# ICEDevice.net
KiCad netlist of a schematic drawn in EAGLE
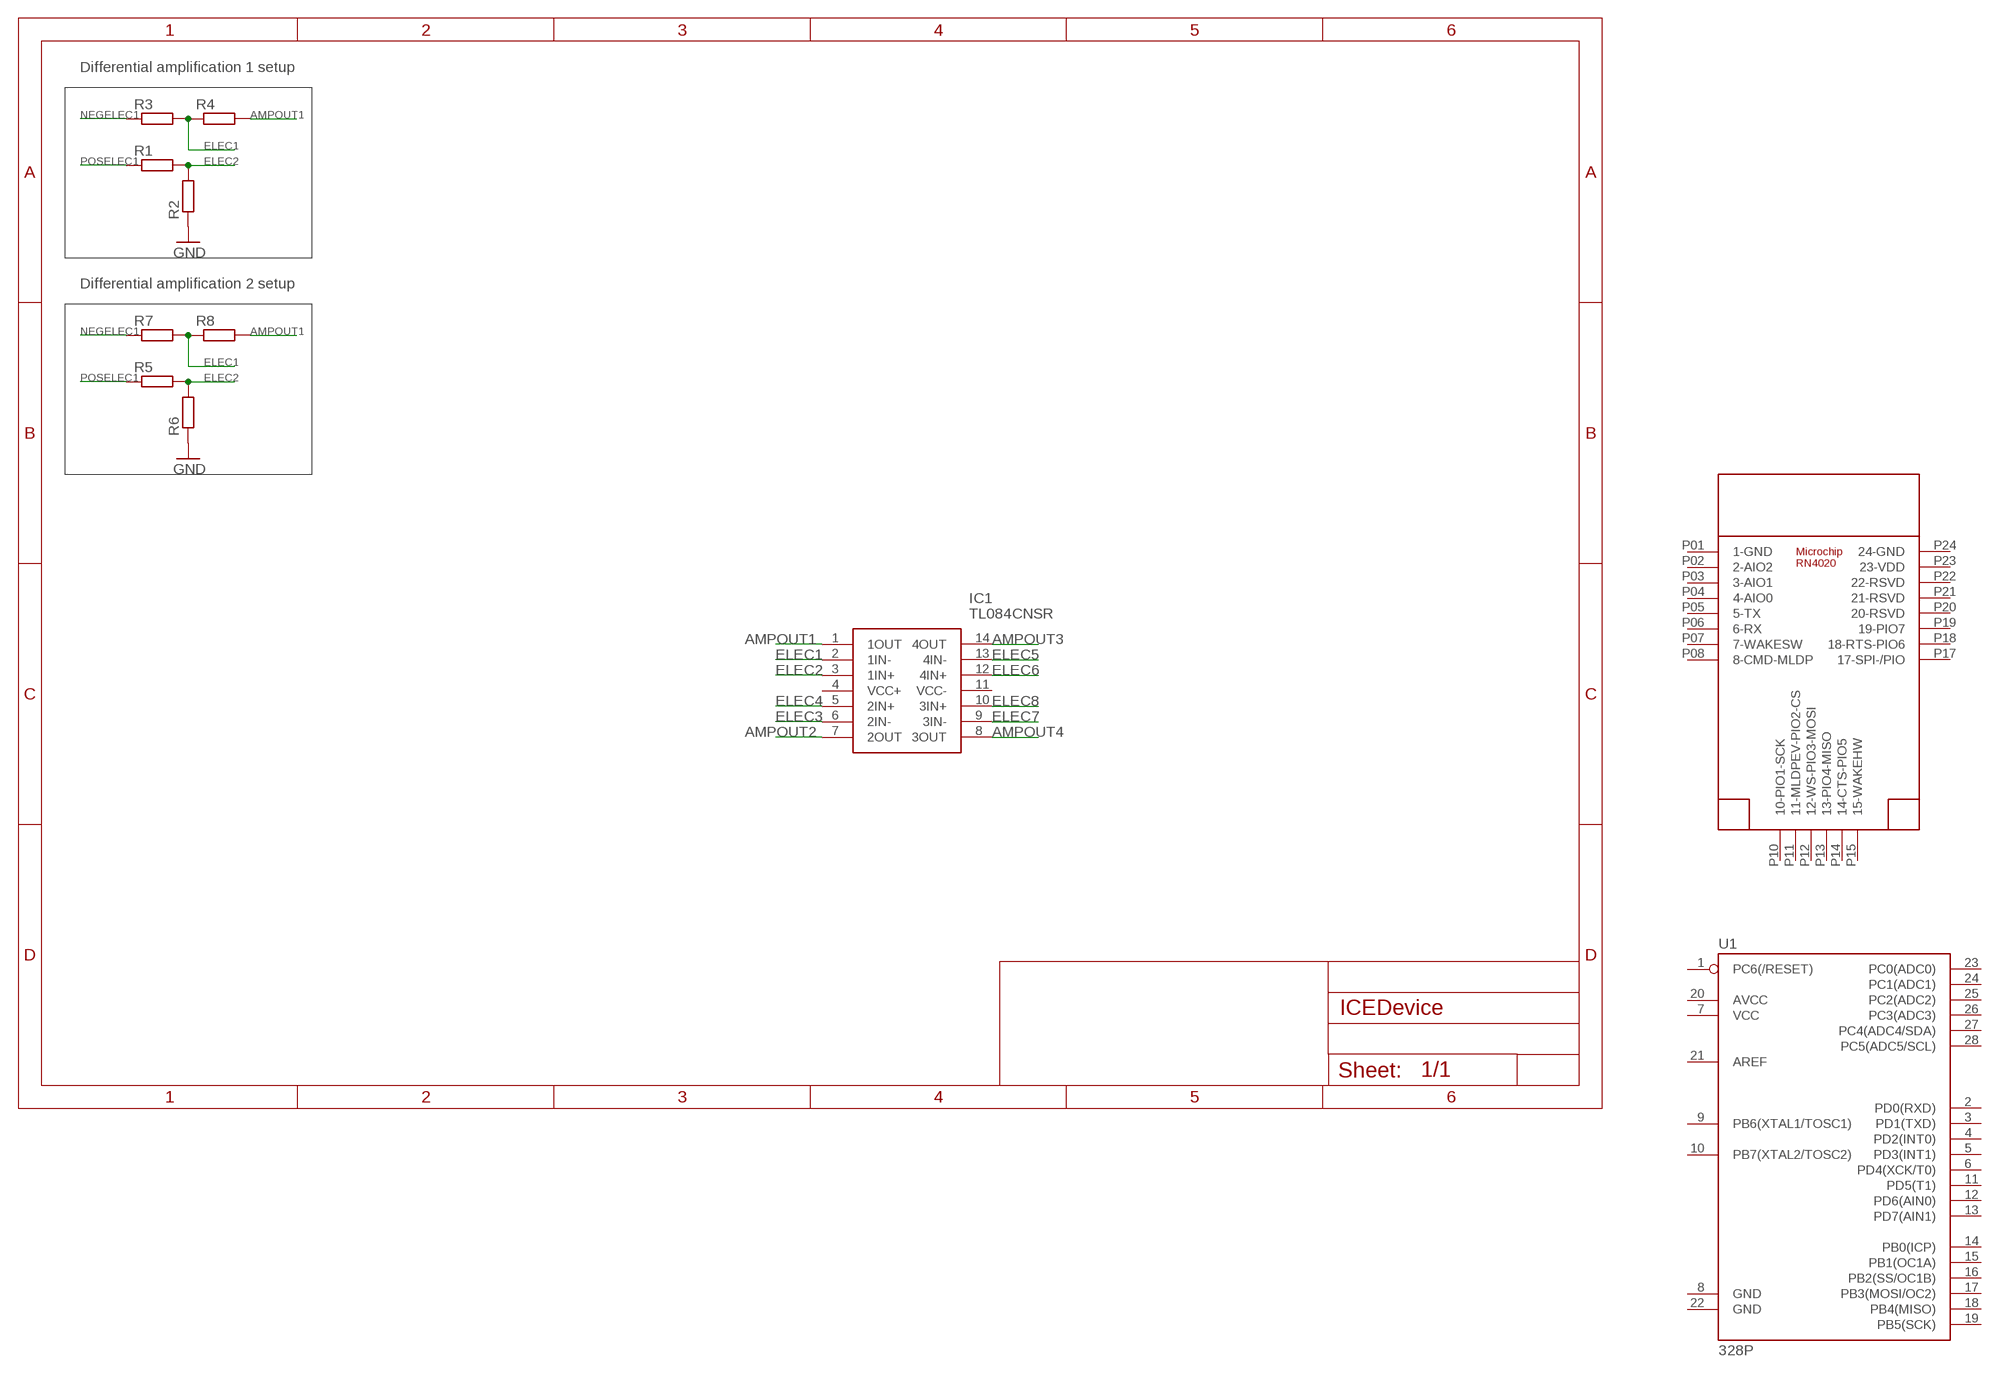
[diagram p0: schematic, sheet 1]

(export (version "E")
  (design (tool "Eeschema 10.0.6"))
  (components
    (comp (ref "IC1")
      (value "TL084CNSR")
      (footprint "eagle-import:SOIC127P780X200-14N")
      (fields (field (name "RS_PART_NUMBER") "1626742"))
      (libsource (lib "eagle-import") (part "TL084CNSR"))
    )
    (comp (ref "R1")
      (value "R-EU_0309/10")
      (footprint "eagle-import:0309_10")
      (libsource (lib "eagle-import") (part "R-EU_0309/10"))
    )
    (comp (ref "R2")
      (value "R-EU_0309/10")
      (footprint "eagle-import:0309_10")
      (libsource (lib "eagle-import") (part "R-EU_0309/10"))
    )
    (comp (ref "R3")
      (value "R-EU_0309/10")
      (footprint "eagle-import:0309_10")
      (libsource (lib "eagle-import") (part "R-EU_0309/10"))
    )
    (comp (ref "R4")
      (value "R-EU_0309/10")
      (footprint "eagle-import:0309_10")
      (libsource (lib "eagle-import") (part "R-EU_0309/10"))
    )
    (comp (ref "R5")
      (value "R-EU_0309/10")
      (footprint "eagle-import:0309_10")
      (libsource (lib "eagle-import") (part "R-EU_0309/10"))
    )
    (comp (ref "R6")
      (value "R-EU_0309/10")
      (footprint "eagle-import:0309_10")
      (libsource (lib "eagle-import") (part "R-EU_0309/10"))
    )
    (comp (ref "R7")
      (value "R-EU_0309/10")
      (footprint "eagle-import:0309_10")
      (libsource (lib "eagle-import") (part "R-EU_0309/10"))
    )
    (comp (ref "R8")
      (value "R-EU_0309/10")
      (footprint "eagle-import:0309_10")
      (libsource (lib "eagle-import") (part "R-EU_0309/10"))
    )
    (comp (ref "U$1")
      (value "RN4020")
      (footprint "eagle-import:RN4020SMD")
      (libsource (lib "eagle-import") (part "RN4020"))
    )
    (comp (ref "U1")
      (value "328P")
      (footprint "eagle-import:DIP28")
      (libsource (lib "eagle-import") (part "ATMEGA328P_PDIP"))
    )
  )
  (nets
    (net (code "1") (name "/AMPOUT1") (class "Default")
      (node (ref "IC1") (pin "1") (pinfunction "1OUT_1") (pintype "bidirectional"))
      (node (ref "R4") (pin "2") (pinfunction "2_2") (pintype "passive"))
      (node (ref "R8") (pin "2") (pinfunction "2_2") (pintype "passive"))
    )
    (net (code "2") (name "/AMPOUT2") (class "Default")
      (node (ref "IC1") (pin "7") (pinfunction "2OUT_7") (pintype "bidirectional"))
    )
    (net (code "3") (name "/AMPOUT3") (class "Default")
      (node (ref "IC1") (pin "14") (pinfunction "4OUT_14") (pintype "bidirectional"))
    )
    (net (code "4") (name "/AMPOUT4") (class "Default")
      (node (ref "IC1") (pin "8") (pinfunction "3OUT_8") (pintype "bidirectional"))
    )
    (net (code "5") (name "/ELEC1") (class "Default")
      (node (ref "IC1") (pin "2") (pinfunction "1IN-_2") (pintype "bidirectional"))
      (node (ref "R3") (pin "2") (pinfunction "2_2") (pintype "passive"))
      (node (ref "R4") (pin "1") (pinfunction "1_1") (pintype "passive"))
      (node (ref "R7") (pin "2") (pinfunction "2_2") (pintype "passive"))
      (node (ref "R8") (pin "1") (pinfunction "1_1") (pintype "passive"))
    )
    (net (code "6") (name "/ELEC2") (class "Default")
      (node (ref "IC1") (pin "3") (pinfunction "1IN+_3") (pintype "bidirectional"))
      (node (ref "R1") (pin "2") (pinfunction "2_2") (pintype "passive"))
      (node (ref "R2") (pin "2") (pinfunction "2_2") (pintype "passive"))
      (node (ref "R5") (pin "2") (pinfunction "2_2") (pintype "passive"))
      (node (ref "R6") (pin "2") (pinfunction "2_2") (pintype "passive"))
    )
    (net (code "7") (name "/ELEC3") (class "Default")
      (node (ref "IC1") (pin "6") (pinfunction "2IN-_6") (pintype "bidirectional"))
    )
    (net (code "8") (name "/ELEC4") (class "Default")
      (node (ref "IC1") (pin "5") (pinfunction "2IN+_5") (pintype "bidirectional"))
    )
    (net (code "9") (name "/ELEC5") (class "Default")
      (node (ref "IC1") (pin "13") (pinfunction "4IN-_13") (pintype "bidirectional"))
    )
    (net (code "10") (name "/ELEC6") (class "Default")
      (node (ref "IC1") (pin "12") (pinfunction "4IN+_12") (pintype "bidirectional"))
    )
    (net (code "11") (name "/ELEC7") (class "Default")
      (node (ref "IC1") (pin "9") (pinfunction "3IN-_9") (pintype "bidirectional"))
    )
    (net (code "12") (name "/ELEC8") (class "Default")
      (node (ref "IC1") (pin "10") (pinfunction "3IN+_10") (pintype "bidirectional"))
    )
    (net (code "13") (name "/NEGELEC1") (class "Default")
      (node (ref "R3") (pin "1") (pinfunction "1_1") (pintype "passive"))
      (node (ref "R7") (pin "1") (pinfunction "1_1") (pintype "passive"))
    )
    (net (code "14") (name "/POSELEC1") (class "Default")
      (node (ref "R1") (pin "1") (pinfunction "1_1") (pintype "passive"))
      (node (ref "R5") (pin "1") (pinfunction "1_1") (pintype "passive"))
    )
    (net (code "15") (name "GND") (class "Default")
      (node (ref "R2") (pin "1") (pinfunction "1_1") (pintype "passive"))
      (node (ref "R6") (pin "1") (pinfunction "1_1") (pintype "passive"))
    )
    (net (code "16") (name "unconnected-(IC1-VCC+-Pad4)") (class "Default")
      (node (ref "IC1") (pin "4") (pinfunction "VCC+_4") (pintype "bidirectional"))
    )
    (net (code "17") (name "unconnected-(IC1-VCC--Pad11)") (class "Default")
      (node (ref "IC1") (pin "11") (pinfunction "VCC-_11") (pintype "bidirectional"))
    )
    (net (code "18") (name "unconnected-(U$1-1-GND-PadP01)") (class "Default")
      (node (ref "U$1") (pin "P01") (pinfunction "1-GND_P01") (pintype "bidirectional"))
    )
    (net (code "19") (name "unconnected-(U$1-2-AIO2-PadP02)") (class "Default")
      (node (ref "U$1") (pin "P02") (pinfunction "2-AIO2_P02") (pintype "bidirectional"))
    )
    (net (code "20") (name "unconnected-(U$1-3-AIO1-PadP03)") (class "Default")
      (node (ref "U$1") (pin "P03") (pinfunction "3-AIO1_P03") (pintype "bidirectional"))
    )
    (net (code "21") (name "unconnected-(U$1-4-AIO0-PadP04)") (class "Default")
      (node (ref "U$1") (pin "P04") (pinfunction "4-AIO0_P04") (pintype "bidirectional"))
    )
    (net (code "22") (name "unconnected-(U$1-5-TX-PadP05)") (class "Default")
      (node (ref "U$1") (pin "P05") (pinfunction "5-TX_P05") (pintype "bidirectional"))
    )
    (net (code "23") (name "unconnected-(U$1-6-RX-PadP06)") (class "Default")
      (node (ref "U$1") (pin "P06") (pinfunction "6-RX_P06") (pintype "bidirectional"))
    )
    (net (code "24") (name "unconnected-(U$1-7-WAKESW-PadP07)") (class "Default")
      (node (ref "U$1") (pin "P07") (pinfunction "7-WAKESW_P07") (pintype "bidirectional"))
    )
    (net (code "25") (name "unconnected-(U$1-8-CMD-MLDP-PadP08)") (class "Default")
      (node (ref "U$1") (pin "P08") (pinfunction "8-CMD-MLDP_P08") (pintype "bidirectional"))
    )
    (net (code "26") (name "unconnected-(U$1-10-PIO1-SCK-PadP10)") (class "Default")
      (node (ref "U$1") (pin "P10") (pinfunction "10-PIO1-SCK_P10") (pintype "bidirectional"))
    )
    (net (code "27") (name "unconnected-(U$1-11-MLDPEV-PIO2-CS-PadP11)") (class "Default")
      (node (ref "U$1") (pin "P11") (pinfunction "11-MLDPEV-PIO2-CS_P11") (pintype "bidirectional"))
    )
    (net (code "28") (name "unconnected-(U$1-12-WS-PIO3-MOSI-PadP12)") (class "Default")
      (node (ref "U$1") (pin "P12") (pinfunction "12-WS-PIO3-MOSI_P12") (pintype "bidirectional"))
    )
    (net (code "29") (name "unconnected-(U$1-13-PIO4-MISO-PadP13)") (class "Default")
      (node (ref "U$1") (pin "P13") (pinfunction "13-PIO4-MISO_P13") (pintype "bidirectional"))
    )
    (net (code "30") (name "unconnected-(U$1-14-CTS-PIO5-PadP14)") (class "Default")
      (node (ref "U$1") (pin "P14") (pinfunction "14-CTS-PIO5_P14") (pintype "bidirectional"))
    )
    (net (code "31") (name "unconnected-(U$1-15-WAKEHW-PadP15)") (class "Default")
      (node (ref "U$1") (pin "P15") (pinfunction "15-WAKEHW_P15") (pintype "bidirectional"))
    )
    (net (code "32") (name "unconnected-(U$1-17-SPI-{slash}PIO-PadP17)") (class "Default")
      (node (ref "U$1") (pin "P17") (pinfunction "17-SPI-/PIO_P17") (pintype "bidirectional"))
    )
    (net (code "33") (name "unconnected-(U$1-18-RTS-PIO6-PadP18)") (class "Default")
      (node (ref "U$1") (pin "P18") (pinfunction "18-RTS-PIO6_P18") (pintype "bidirectional"))
    )
    (net (code "34") (name "unconnected-(U$1-19-PIO7-PadP19)") (class "Default")
      (node (ref "U$1") (pin "P19") (pinfunction "19-PIO7_P19") (pintype "bidirectional"))
    )
    (net (code "35") (name "unconnected-(U$1-20-RSVD-PadP20)") (class "Default")
      (node (ref "U$1") (pin "P20") (pinfunction "20-RSVD_P20") (pintype "bidirectional"))
    )
    (net (code "36") (name "unconnected-(U$1-21-RSVD-PadP21)") (class "Default")
      (node (ref "U$1") (pin "P21") (pinfunction "21-RSVD_P21") (pintype "bidirectional"))
    )
    (net (code "37") (name "unconnected-(U$1-22-RSVD-PadP22)") (class "Default")
      (node (ref "U$1") (pin "P22") (pinfunction "22-RSVD_P22") (pintype "bidirectional"))
    )
    (net (code "38") (name "unconnected-(U$1-23-VDD-PadP23)") (class "Default")
      (node (ref "U$1") (pin "P23") (pinfunction "23-VDD_P23") (pintype "bidirectional"))
    )
    (net (code "39") (name "unconnected-(U$1-24-GND-PadP24)") (class "Default")
      (node (ref "U$1") (pin "P24") (pinfunction "24-GND_P24") (pintype "bidirectional"))
    )
    (net (code "40") (name "unconnected-(U1-AREF-Pad21)") (class "Default")
      (node (ref "U1") (pin "21") (pinfunction "AREF_21") (pintype "bidirectional"))
    )
    (net (code "41") (name "unconnected-(U1-AVCC-Pad20)") (class "Default")
      (node (ref "U1") (pin "20") (pinfunction "AVCC_20") (pintype "bidirectional"))
    )
    (net (code "42") (name "unconnected-(U1-GND-Pad8)") (class "Default")
      (node (ref "U1") (pin "8") (pinfunction "GND_8") (pintype "bidirectional"))
    )
    (net (code "43") (name "unconnected-(U1-GND-Pad22)") (class "Default")
      (node (ref "U1") (pin "22") (pinfunction "GND_22") (pintype "bidirectional"))
    )
    (net (code "44") (name "unconnected-(U1-PB0(ICP)-Pad14)") (class "Default")
      (node (ref "U1") (pin "14") (pinfunction "PB0(ICP)_14") (pintype "bidirectional"))
    )
    (net (code "45") (name "unconnected-(U1-PB1(OC1A)-Pad15)") (class "Default")
      (node (ref "U1") (pin "15") (pinfunction "PB1(OC1A)_15") (pintype "bidirectional"))
    )
    (net (code "46") (name "unconnected-(U1-PB2(SS{slash}OC1B)-Pad16)") (class "Default")
      (node (ref "U1") (pin "16") (pinfunction "PB2(SS/OC1B)_16") (pintype "bidirectional"))
    )
    (net (code "47") (name "unconnected-(U1-PB3(MOSI{slash}OC2)-Pad17)") (class "Default")
      (node (ref "U1") (pin "17") (pinfunction "PB3(MOSI/OC2)_17") (pintype "bidirectional"))
    )
    (net (code "48") (name "unconnected-(U1-PB4(MISO)-Pad18)") (class "Default")
      (node (ref "U1") (pin "18") (pinfunction "PB4(MISO)_18") (pintype "bidirectional"))
    )
    (net (code "49") (name "unconnected-(U1-PB5(SCK)-Pad19)") (class "Default")
      (node (ref "U1") (pin "19") (pinfunction "PB5(SCK)_19") (pintype "bidirectional"))
    )
    (net (code "50") (name "unconnected-(U1-PB6(XTAL1{slash}TOSC1)-Pad9)") (class "Default")
      (node (ref "U1") (pin "9") (pinfunction "PB6(XTAL1/TOSC1)_9") (pintype "bidirectional"))
    )
    (net (code "51") (name "unconnected-(U1-PB7(XTAL2{slash}TOSC2)-Pad10)") (class "Default")
      (node (ref "U1") (pin "10") (pinfunction "PB7(XTAL2/TOSC2)_10") (pintype "bidirectional"))
    )
    (net (code "52") (name "unconnected-(U1-PC0(ADC0)-Pad23)") (class "Default")
      (node (ref "U1") (pin "23") (pinfunction "PC0(ADC0)_23") (pintype "bidirectional"))
    )
    (net (code "53") (name "unconnected-(U1-PC1(ADC1)-Pad24)") (class "Default")
      (node (ref "U1") (pin "24") (pinfunction "PC1(ADC1)_24") (pintype "bidirectional"))
    )
    (net (code "54") (name "unconnected-(U1-PC2(ADC2)-Pad25)") (class "Default")
      (node (ref "U1") (pin "25") (pinfunction "PC2(ADC2)_25") (pintype "bidirectional"))
    )
    (net (code "55") (name "unconnected-(U1-PC3(ADC3)-Pad26)") (class "Default")
      (node (ref "U1") (pin "26") (pinfunction "PC3(ADC3)_26") (pintype "bidirectional"))
    )
    (net (code "56") (name "unconnected-(U1-PC4(ADC4{slash}SDA)-Pad27)") (class "Default")
      (node (ref "U1") (pin "27") (pinfunction "PC4(ADC4/SDA)_27") (pintype "bidirectional"))
    )
    (net (code "57") (name "unconnected-(U1-PC5(ADC5{slash}SCL)-Pad28)") (class "Default")
      (node (ref "U1") (pin "28") (pinfunction "PC5(ADC5/SCL)_28") (pintype "bidirectional"))
    )
    (net (code "58") (name "unconnected-(U1-PC6({slash}RESET)-Pad1)") (class "Default")
      (node (ref "U1") (pin "1") (pinfunction "PC6(/RESET)_1") (pintype "bidirectional"))
    )
    (net (code "59") (name "unconnected-(U1-PD0(RXD)-Pad2)") (class "Default")
      (node (ref "U1") (pin "2") (pinfunction "PD0(RXD)_2") (pintype "bidirectional"))
    )
    (net (code "60") (name "unconnected-(U1-PD1(TXD)-Pad3)") (class "Default")
      (node (ref "U1") (pin "3") (pinfunction "PD1(TXD)_3") (pintype "bidirectional"))
    )
    (net (code "61") (name "unconnected-(U1-PD2(INT0)-Pad4)") (class "Default")
      (node (ref "U1") (pin "4") (pinfunction "PD2(INT0)_4") (pintype "bidirectional"))
    )
    (net (code "62") (name "unconnected-(U1-PD3(INT1)-Pad5)") (class "Default")
      (node (ref "U1") (pin "5") (pinfunction "PD3(INT1)_5") (pintype "bidirectional"))
    )
    (net (code "63") (name "unconnected-(U1-PD4(XCK{slash}T0)-Pad6)") (class "Default")
      (node (ref "U1") (pin "6") (pinfunction "PD4(XCK/T0)_6") (pintype "bidirectional"))
    )
    (net (code "64") (name "unconnected-(U1-PD5(T1)-Pad11)") (class "Default")
      (node (ref "U1") (pin "11") (pinfunction "PD5(T1)_11") (pintype "bidirectional"))
    )
    (net (code "65") (name "unconnected-(U1-PD6(AIN0)-Pad12)") (class "Default")
      (node (ref "U1") (pin "12") (pinfunction "PD6(AIN0)_12") (pintype "bidirectional"))
    )
    (net (code "66") (name "unconnected-(U1-PD7(AIN1)-Pad13)") (class "Default")
      (node (ref "U1") (pin "13") (pinfunction "PD7(AIN1)_13") (pintype "bidirectional"))
    )
    (net (code "67") (name "unconnected-(U1-VCC-Pad7)") (class "Default")
      (node (ref "U1") (pin "7") (pinfunction "VCC_7") (pintype "bidirectional"))
    )
  )
)
